# edison_mezzanine_9dof.net
KiCad netlist of a schematic drawn in EAGLE
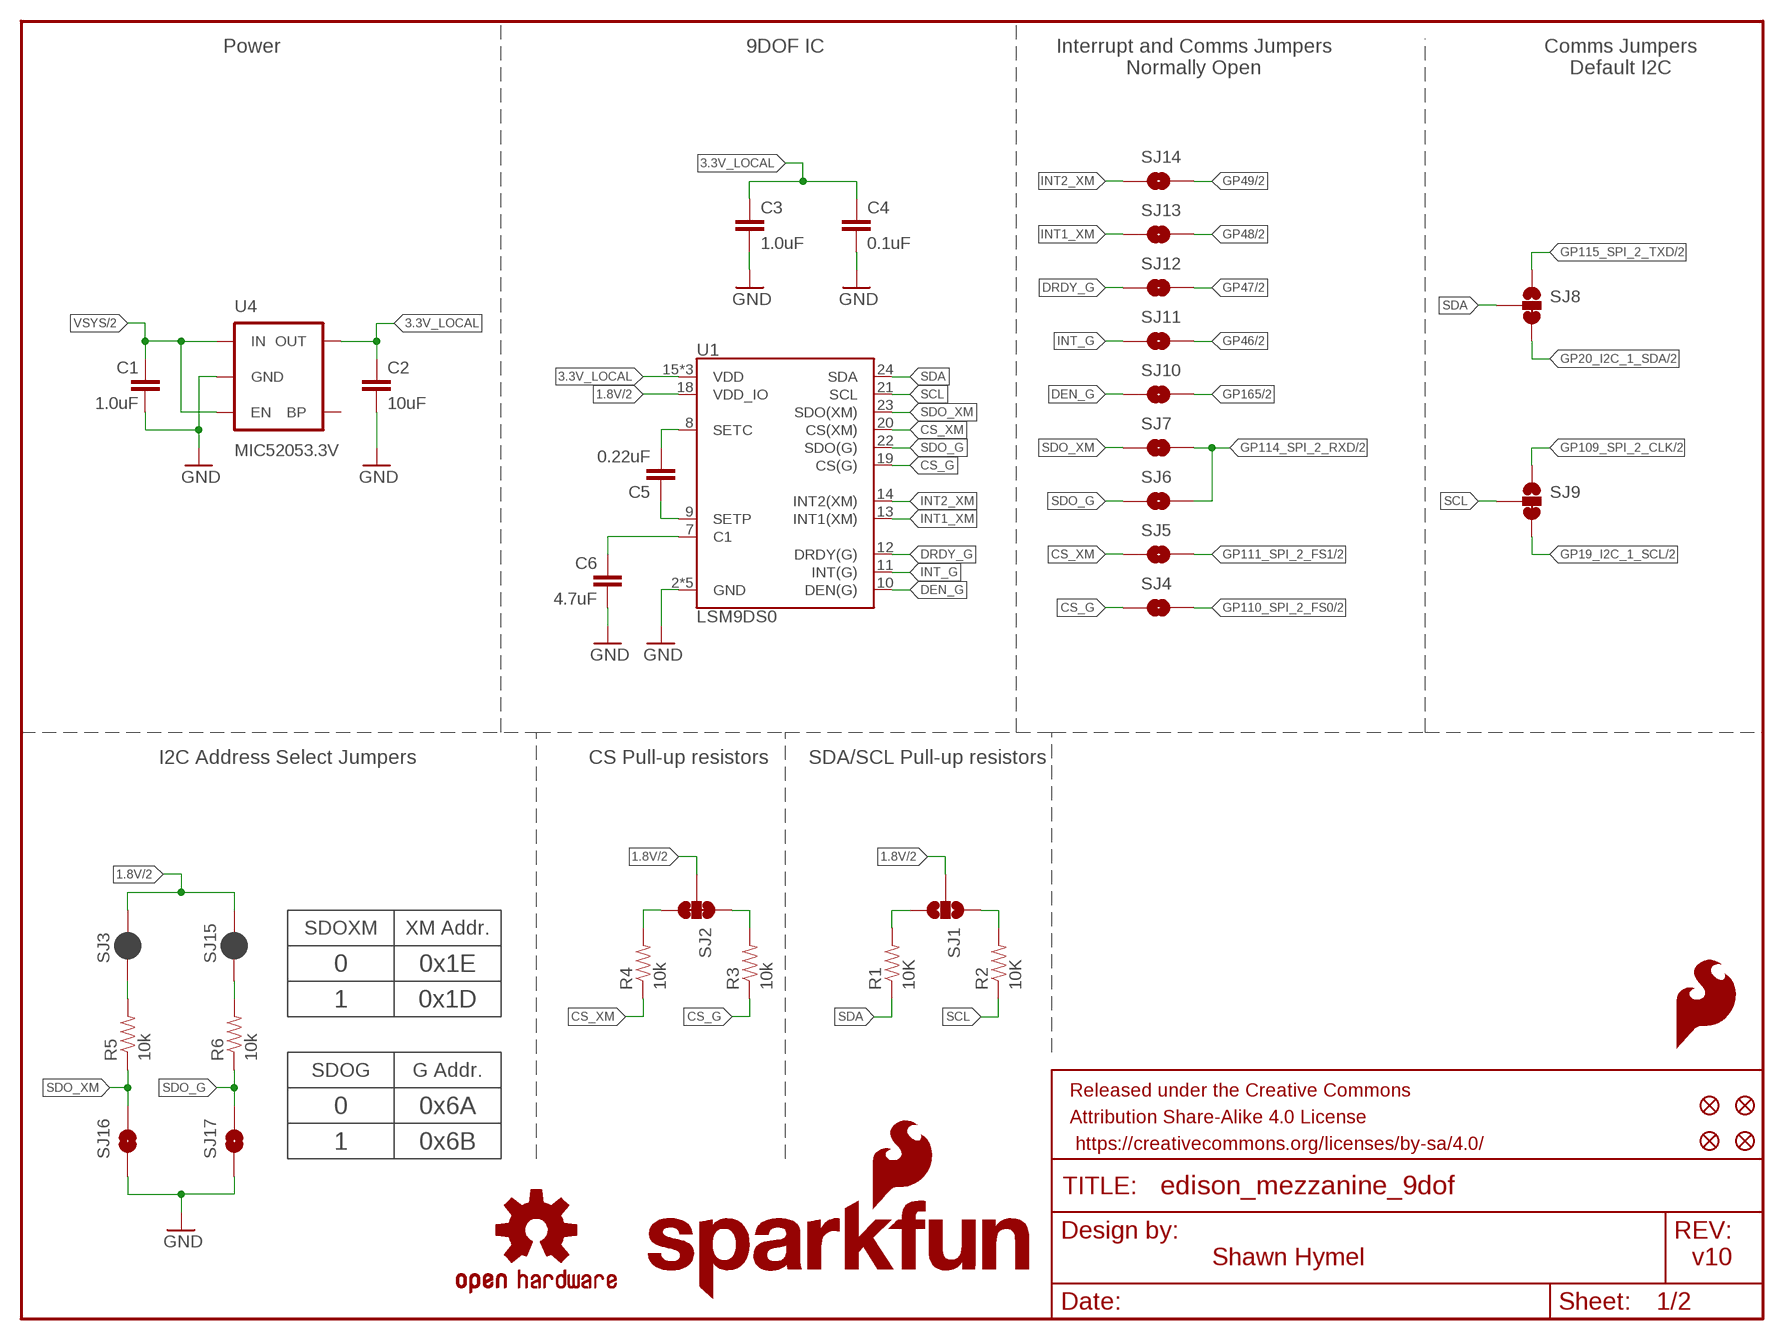
[diagram p0: schematic, sheet 1]
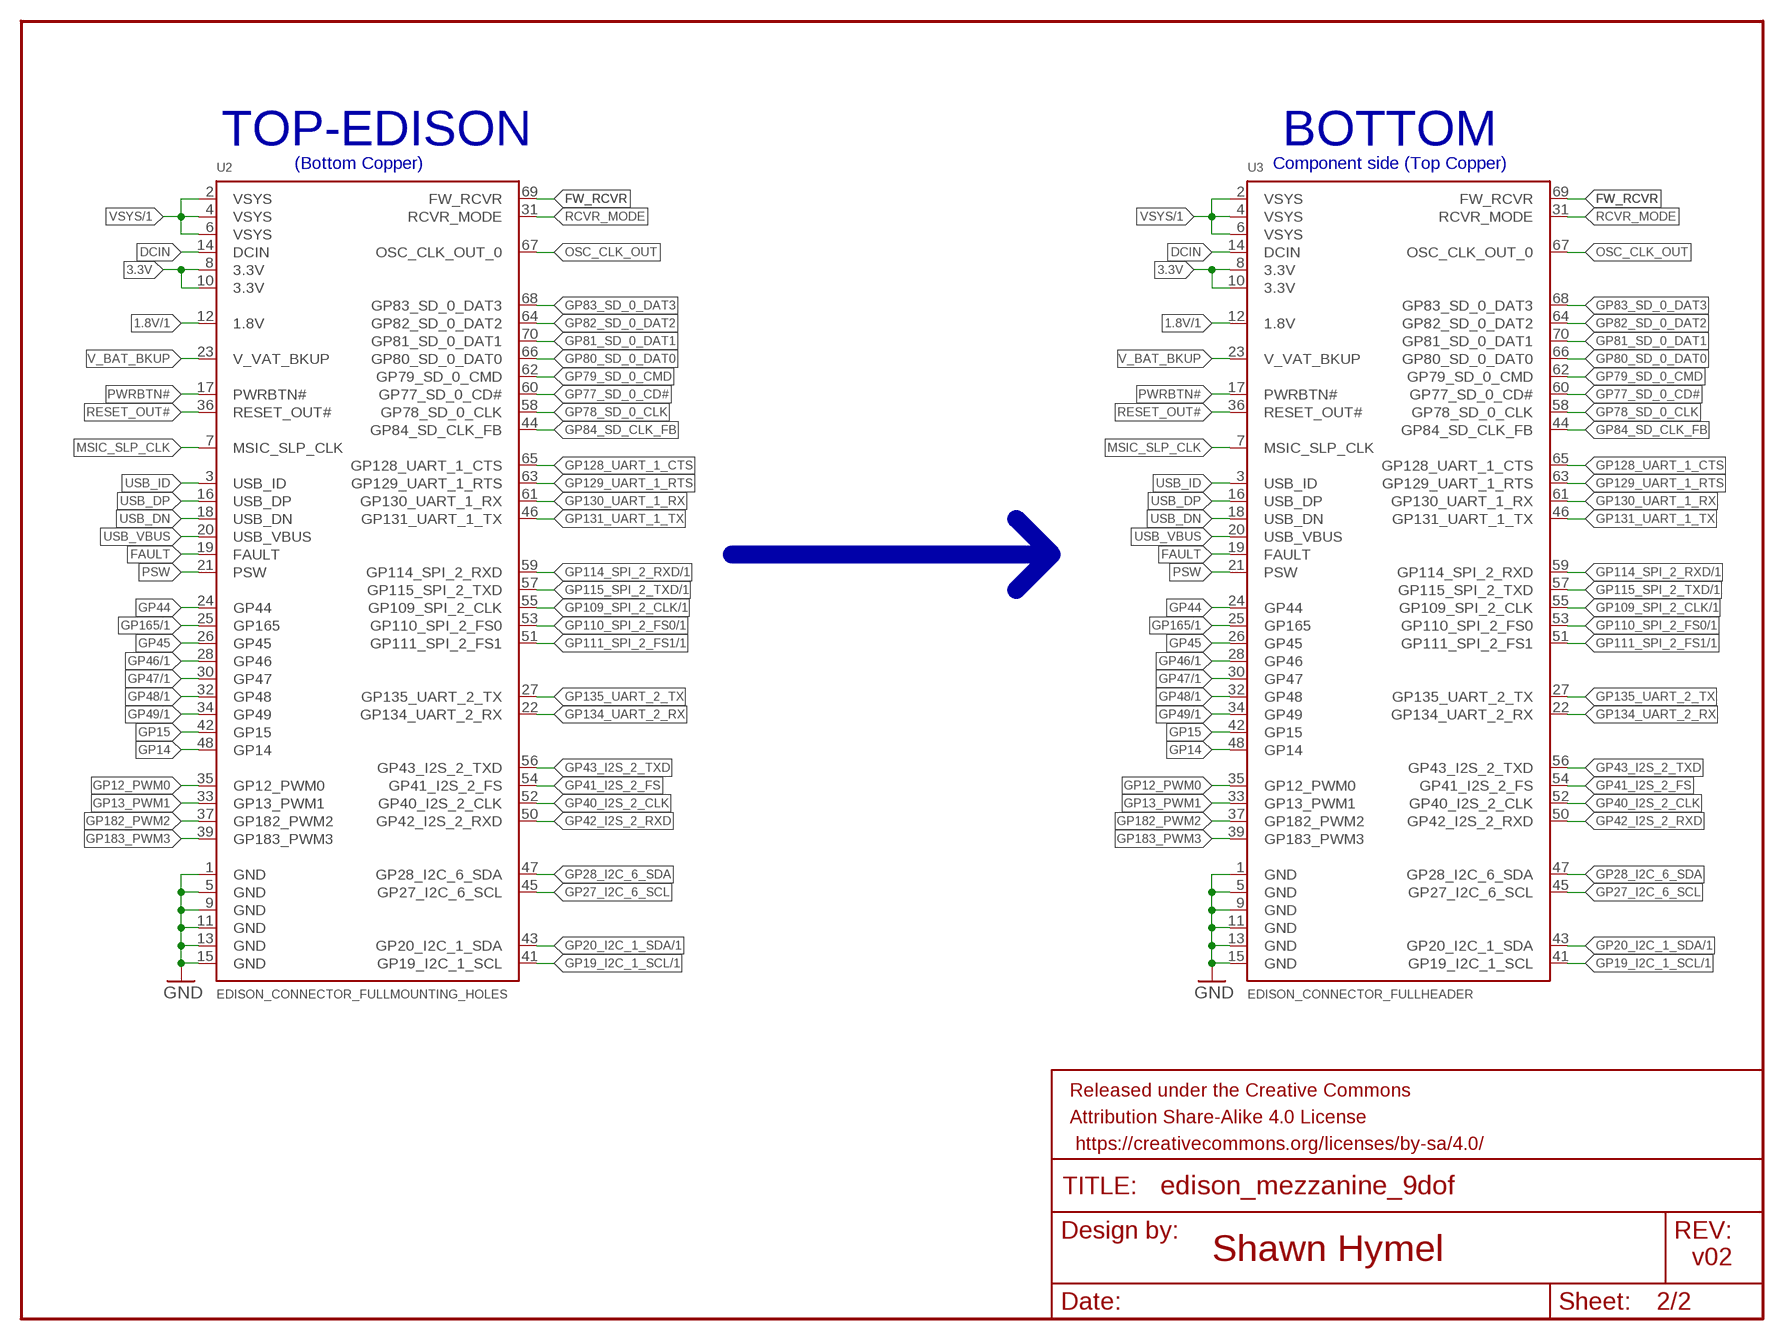
[diagram p1: schematic, sheet 2]

(export (version "E")
  (design (tool "Eeschema 10.0.6"))
  (components
    (comp (ref "C1")
      (value "1.0uF")
      (footprint "eagle-import:0603-CAP")
      (libsource (lib "eagle-import") (part "1.0UF-16V-10%(0603)"))
    )
    (comp (ref "C2")
      (value "10uF")
      (footprint "eagle-import:0805")
      (libsource (lib "eagle-import") (part "CAP0805"))
    )
    (comp (ref "C3")
      (value "1.0uF")
      (footprint "eagle-import:0603-CAP")
      (libsource (lib "eagle-import") (part "1.0UF-16V-10%(0603)"))
    )
    (comp (ref "C4")
      (value "0.1uF")
      (footprint "eagle-import:0603-CAP")
      (libsource (lib "eagle-import") (part "0.1UF-25V(+80/-20%)(0603)"))
    )
    (comp (ref "C5")
      (value "0.22uF")
      (footprint "eagle-import:0603-CAP")
      (libsource (lib "eagle-import") (part "0.22UF-25V-10%(0603)"))
    )
    (comp (ref "C6")
      (value "4.7uF")
      (footprint "eagle-import:0603-CAP")
      (libsource (lib "eagle-import") (part "4.7UF-6.3V-10%(0603)0603"))
    )
    (comp (ref "FID1")
      (value "FIDUCIAL1X2")
      (footprint "eagle-import:FIDUCIAL-1X2")
      (libsource (lib "eagle-import") (part "FIDUCIAL1X2"))
    )
    (comp (ref "FID2")
      (value "FIDUCIAL1X2")
      (footprint "eagle-import:FIDUCIAL-1X2")
      (libsource (lib "eagle-import") (part "FIDUCIAL1X2"))
    )
    (comp (ref "FID3")
      (value "FIDUCIAL1X2")
      (footprint "eagle-import:FIDUCIAL-1X2")
      (libsource (lib "eagle-import") (part "FIDUCIAL1X2"))
    )
    (comp (ref "FID4")
      (value "FIDUCIAL1X2")
      (footprint "eagle-import:FIDUCIAL-1X2")
      (libsource (lib "eagle-import") (part "FIDUCIAL1X2"))
    )
    (comp (ref "FRAME1")
      (value "FRAME-LETTER")
      (footprint "eagle-import:CREATIVE_COMMONS")
      (libsource (lib "eagle-import") (part "FRAME-LETTER"))
    )
    (comp (ref "LOGO1")
      (value "SFE_LOGO_FLAME.2_INCH")
      (footprint "eagle-import:SFE_LOGO_FLAME_.2")
      (libsource (lib "eagle-import") (part "SFE_LOGO_FLAME.2_INCH"))
    )
    (comp (ref "LOGO2")
      (value "OSHW-LOGOS")
      (footprint "eagle-import:OSHW-LOGO-S")
      (libsource (lib "eagle-import") (part "OSHW-LOGOS"))
    )
    (comp (ref "LOGO3")
      (value "SFE_LOGO_NAME_FLAME.1_INCH")
      (footprint "eagle-import:SFE_LOGO_NAME_FLAME_.1")
      (libsource (lib "eagle-import") (part "SFE_LOGO_NAME_FLAME.1_INCH"))
    )
    (comp (ref "R1")
      (value "10K")
      (footprint "eagle-import:0603-RES")
      (libsource (lib "eagle-import") (part "10KOHM1/10W1%(0603)0603"))
    )
    (comp (ref "R2")
      (value "10K")
      (footprint "eagle-import:0603-RES")
      (libsource (lib "eagle-import") (part "10KOHM1/10W1%(0603)0603"))
    )
    (comp (ref "R3")
      (value "10k")
      (footprint "eagle-import:0603-RES")
      (libsource (lib "eagle-import") (part "10K-1%RES-00824"))
    )
    (comp (ref "R4")
      (value "10k")
      (footprint "eagle-import:0603-RES")
      (libsource (lib "eagle-import") (part "10K-1%RES-00824"))
    )
    (comp (ref "R5")
      (value "10k")
      (footprint "eagle-import:0603-RES")
      (libsource (lib "eagle-import") (part "10K-1%RES-00824"))
    )
    (comp (ref "R6")
      (value "10k")
      (footprint "eagle-import:0603-RES")
      (libsource (lib "eagle-import") (part "10K-1%RES-00824"))
    )
    (comp (ref "SJ1")
      (value "JUMPER-PAD-3-NOYES_SILK")
      (footprint "eagle-import:PAD-JUMPER-3-NO_YES_SILK")
      (libsource (lib "eagle-import") (part "JUMPER-PAD-3-NOYES_SILK"))
    )
    (comp (ref "SJ2")
      (value "JUMPER-PAD-3-NC_BY_TRACE")
      (footprint "eagle-import:PAD-JUMPER-3-3OF3_NC_BY_TRACE_YES_SILK_FULL_BOX")
      (libsource (lib "eagle-import") (part "JUMPER-PAD-3-NC_BY_TRACE"))
    )
    (comp (ref "SJ3")
      (value "JUMPER-PAD-2-NC_BY_PASTE")
      (footprint "eagle-import:PAD-JUMPER-2-NC_BY_PASTE_YES_SILK")
      (libsource (lib "eagle-import") (part "JUMPER-PAD-2-NC_BY_PASTE"))
    )
    (comp (ref "SJ4")
      (value "JUMPER-PAD-2-NOYES_SILK")
      (footprint "eagle-import:PAD-JUMPER-2-NO_YES_SILK")
      (libsource (lib "eagle-import") (part "JUMPER-PAD-2-NOYES_SILK"))
    )
    (comp (ref "SJ5")
      (value "JUMPER-PAD-2-NOYES_SILK")
      (footprint "eagle-import:PAD-JUMPER-2-NO_YES_SILK")
      (libsource (lib "eagle-import") (part "JUMPER-PAD-2-NOYES_SILK"))
    )
    (comp (ref "SJ6")
      (value "JUMPER-PAD-2-NOYES_SILK")
      (footprint "eagle-import:PAD-JUMPER-2-NO_YES_SILK")
      (libsource (lib "eagle-import") (part "JUMPER-PAD-2-NOYES_SILK"))
    )
    (comp (ref "SJ7")
      (value "JUMPER-PAD-2-NOYES_SILK")
      (footprint "eagle-import:PAD-JUMPER-2-NO_YES_SILK")
      (libsource (lib "eagle-import") (part "JUMPER-PAD-2-NOYES_SILK"))
    )
    (comp (ref "SJ8")
      (value "JUMPER-PAD-3-2OF3_NC_BY_TRACE_SMALL")
      (footprint "eagle-import:PAD-JUMPER-3-2OF3_NC_BY_TRACE_YES_SILK_FULL_BOX")
      (libsource (lib "eagle-import") (part "JUMPER-PAD-3-2OF3_NC_BY_TRACE_SMALL"))
    )
    (comp (ref "SJ9")
      (value "JUMPER-PAD-3-2OF3_NC_BY_TRACE_SMALL")
      (footprint "eagle-import:PAD-JUMPER-3-2OF3_NC_BY_TRACE_YES_SILK_FULL_BOX")
      (libsource (lib "eagle-import") (part "JUMPER-PAD-3-2OF3_NC_BY_TRACE_SMALL"))
    )
    (comp (ref "SJ10")
      (value "JUMPER-PAD-2-NOYES_SILK")
      (footprint "eagle-import:PAD-JUMPER-2-NO_YES_SILK")
      (libsource (lib "eagle-import") (part "JUMPER-PAD-2-NOYES_SILK"))
    )
    (comp (ref "SJ11")
      (value "JUMPER-PAD-2-NOYES_SILK")
      (footprint "eagle-import:PAD-JUMPER-2-NO_YES_SILK")
      (libsource (lib "eagle-import") (part "JUMPER-PAD-2-NOYES_SILK"))
    )
    (comp (ref "SJ12")
      (value "JUMPER-PAD-2-NOYES_SILK")
      (footprint "eagle-import:PAD-JUMPER-2-NO_YES_SILK")
      (libsource (lib "eagle-import") (part "JUMPER-PAD-2-NOYES_SILK"))
    )
    (comp (ref "SJ13")
      (value "JUMPER-PAD-2-NOYES_SILK")
      (footprint "eagle-import:PAD-JUMPER-2-NO_YES_SILK")
      (libsource (lib "eagle-import") (part "JUMPER-PAD-2-NOYES_SILK"))
    )
    (comp (ref "SJ14")
      (value "JUMPER-PAD-2-NOYES_SILK")
      (footprint "eagle-import:PAD-JUMPER-2-NO_YES_SILK")
      (libsource (lib "eagle-import") (part "JUMPER-PAD-2-NOYES_SILK"))
    )
    (comp (ref "SJ15")
      (value "JUMPER-PAD-2-NC_BY_PASTE")
      (footprint "eagle-import:PAD-JUMPER-2-NC_BY_PASTE_YES_SILK")
      (libsource (lib "eagle-import") (part "JUMPER-PAD-2-NC_BY_PASTE"))
    )
    (comp (ref "SJ16")
      (value "JUMPER-PAD-2-NOYES_SILK")
      (footprint "eagle-import:PAD-JUMPER-2-NO_YES_SILK")
      (libsource (lib "eagle-import") (part "JUMPER-PAD-2-NOYES_SILK"))
    )
    (comp (ref "SJ17")
      (value "JUMPER-PAD-2-NOYES_SILK")
      (footprint "eagle-import:PAD-JUMPER-2-NO_YES_SILK")
      (libsource (lib "eagle-import") (part "JUMPER-PAD-2-NOYES_SILK"))
    )
    (comp (ref "U1")
      (value "LSM9DS0")
      (footprint "eagle-import:LGA-24")
      (libsource (lib "eagle-import") (part "LSM9DS0"))
    )
    (comp (ref "U4")
      (value "MIC52053.3V")
      (footprint "eagle-import:SOT23-5")
      (libsource (lib "eagle-import") (part "MIC52053.3V"))
    )
    (comp (ref "FRAME2")
      (value "FRAME-LETTER")
      (footprint "eagle-import:CREATIVE_COMMONS")
      (libsource (lib "eagle-import") (part "FRAME-LETTER"))
    )
    (comp (ref "U2")
      (value "EDISON_CONNECTOR_FULLMOUNTING_HOLES")
      (footprint "eagle-import:EDISON_DAUGHTER")
      (libsource (lib "eagle-import") (part "EDISON_CONNECTOR_FULLMOUNTING_HOLES"))
    )
    (comp (ref "U3")
      (value "EDISON_CONNECTOR_FULLHEADER")
      (footprint "eagle-import:DF40C-70DP-0.4(51)")
      (libsource (lib "eagle-import") (part "EDISON_CONNECTOR_FULLHEADER"))
    )
  )
  (nets
    (net (code "1") (name "1.8V") (class "Default")
      (node (ref "SJ1") (pin "2") (pinfunction "2_2") (pintype "passive"))
      (node (ref "SJ15") (pin "2") (pinfunction "2_2") (pintype "passive"))
      (node (ref "SJ2") (pin "2") (pinfunction "2_2") (pintype "passive"))
      (node (ref "SJ3") (pin "2") (pinfunction "2_2") (pintype "passive"))
      (node (ref "U1") (pin "18") (pinfunction "VDD_IO_18") (pintype "bidirectional"))
      (node (ref "U2") (pin "12") (pinfunction "1.8V_12") (pintype "bidirectional"))
      (node (ref "U3") (pin "12") (pinfunction "1.8V_12") (pintype "bidirectional"))
    )
    (net (code "2") (name "3.3V") (class "Default")
      (node (ref "U2") (pin "10") (pinfunction "3.3V_10") (pintype "bidirectional"))
      (node (ref "U2") (pin "8") (pinfunction "3.3V_8") (pintype "bidirectional"))
      (node (ref "U3") (pin "10") (pinfunction "3.3V_10") (pintype "bidirectional"))
      (node (ref "U3") (pin "8") (pinfunction "3.3V_8") (pintype "bidirectional"))
    )
    (net (code "3") (name "3.3V_LOCAL") (class "Default")
      (node (ref "C2") (pin "1") (pinfunction "1_1") (pintype "passive"))
      (node (ref "C3") (pin "1") (pinfunction "1_1") (pintype "passive"))
      (node (ref "C4") (pin "1") (pinfunction "1_1") (pintype "passive"))
      (node (ref "U1") (pin "15") (pinfunction "VDD_15") (pintype "bidirectional"))
      (node (ref "U1") (pin "16") (pinfunction "VDD_16") (pintype "bidirectional"))
      (node (ref "U1") (pin "17") (pinfunction "VDD_17") (pintype "bidirectional"))
      (node (ref "U4") (pin "5") (pinfunction "OUT_5") (pintype "passive"))
    )
    (net (code "4") (name "CS_G") (class "Default")
      (node (ref "R3") (pin "1") (pinfunction "1_1") (pintype "passive"))
      (node (ref "SJ4") (pin "1") (pinfunction "1_1") (pintype "passive"))
      (node (ref "U1") (pin "19") (pinfunction "CS(G)_19") (pintype "bidirectional"))
    )
    (net (code "5") (name "CS_XM") (class "Default")
      (node (ref "R4") (pin "1") (pinfunction "1_1") (pintype "passive"))
      (node (ref "SJ5") (pin "1") (pinfunction "1_1") (pintype "passive"))
      (node (ref "U1") (pin "20") (pinfunction "CS(XM)_20") (pintype "bidirectional"))
    )
    (net (code "6") (name "DCIN") (class "Default")
      (node (ref "U2") (pin "14") (pinfunction "DCIN_14") (pintype "bidirectional"))
      (node (ref "U3") (pin "14") (pinfunction "DCIN_14") (pintype "bidirectional"))
    )
    (net (code "7") (name "DEN_G") (class "Default")
      (node (ref "SJ10") (pin "1") (pinfunction "1_1") (pintype "passive"))
      (node (ref "U1") (pin "10") (pinfunction "DEN(G)_10") (pintype "bidirectional"))
    )
    (net (code "8") (name "DRDY_G") (class "Default")
      (node (ref "SJ12") (pin "1") (pinfunction "1_1") (pintype "passive"))
      (node (ref "U1") (pin "12") (pinfunction "DRDY(G)_12") (pintype "bidirectional"))
    )
    (net (code "9") (name "FAULT") (class "Default")
      (node (ref "U2") (pin "19") (pinfunction "FAULT_19") (pintype "bidirectional"))
      (node (ref "U3") (pin "19") (pinfunction "FAULT_19") (pintype "bidirectional"))
    )
    (net (code "10") (name "FW_RCVR") (class "Default")
      (node (ref "U2") (pin "69") (pinfunction "FW_RCVR_69") (pintype "bidirectional"))
      (node (ref "U3") (pin "69") (pinfunction "FW_RCVR_69") (pintype "bidirectional"))
    )
    (net (code "11") (name "GND") (class "Default")
      (node (ref "C1") (pin "2") (pinfunction "2_2") (pintype "passive"))
      (node (ref "C2") (pin "2") (pinfunction "2_2") (pintype "passive"))
      (node (ref "C3") (pin "2") (pinfunction "2_2") (pintype "passive"))
      (node (ref "C4") (pin "2") (pinfunction "2_2") (pintype "passive"))
      (node (ref "C6") (pin "2") (pinfunction "2_2") (pintype "passive"))
      (node (ref "SJ16") (pin "1") (pinfunction "1_1") (pintype "passive"))
      (node (ref "SJ17") (pin "1") (pinfunction "1_1") (pintype "passive"))
      (node (ref "U1") (pin "2") (pinfunction "GND_2") (pintype "bidirectional"))
      (node (ref "U1") (pin "3") (pinfunction "GND_3") (pintype "bidirectional"))
      (node (ref "U1") (pin "4") (pinfunction "GND_4") (pintype "bidirectional"))
      (node (ref "U1") (pin "5") (pinfunction "GND_5") (pintype "bidirectional"))
      (node (ref "U1") (pin "6") (pinfunction "GND_6") (pintype "bidirectional"))
      (node (ref "U2") (pin "1") (pinfunction "GND_1") (pintype "bidirectional"))
      (node (ref "U2") (pin "11") (pinfunction "GND_11") (pintype "bidirectional"))
      (node (ref "U2") (pin "13") (pinfunction "GND_13") (pintype "bidirectional"))
      (node (ref "U2") (pin "15") (pinfunction "GND_15") (pintype "bidirectional"))
      (node (ref "U2") (pin "5") (pinfunction "GND_5") (pintype "bidirectional"))
      (node (ref "U2") (pin "9") (pinfunction "GND_9") (pintype "bidirectional"))
      (node (ref "U3") (pin "1") (pinfunction "GND_1") (pintype "bidirectional"))
      (node (ref "U3") (pin "11") (pinfunction "GND_11") (pintype "bidirectional"))
      (node (ref "U3") (pin "13") (pinfunction "GND_13") (pintype "bidirectional"))
      (node (ref "U3") (pin "15") (pinfunction "GND_15") (pintype "bidirectional"))
      (node (ref "U3") (pin "5") (pinfunction "GND_5") (pintype "bidirectional"))
      (node (ref "U3") (pin "9") (pinfunction "GND_9") (pintype "bidirectional"))
      (node (ref "U4") (pin "2") (pinfunction "GND_2") (pintype "input"))
    )
    (net (code "12") (name "GP12_PWM0") (class "Default")
      (node (ref "U2") (pin "35") (pinfunction "GP12_PWM0_35") (pintype "bidirectional"))
      (node (ref "U3") (pin "35") (pinfunction "GP12_PWM0_35") (pintype "bidirectional"))
    )
    (net (code "13") (name "GP13_PWM1") (class "Default")
      (node (ref "U2") (pin "33") (pinfunction "GP13_PWM1_33") (pintype "bidirectional"))
      (node (ref "U3") (pin "33") (pinfunction "GP13_PWM1_33") (pintype "bidirectional"))
    )
    (net (code "14") (name "GP14") (class "Default")
      (node (ref "U2") (pin "48") (pinfunction "GP14_48") (pintype "bidirectional"))
      (node (ref "U3") (pin "48") (pinfunction "GP14_48") (pintype "bidirectional"))
    )
    (net (code "15") (name "GP15") (class "Default")
      (node (ref "U2") (pin "42") (pinfunction "GP15_42") (pintype "bidirectional"))
      (node (ref "U3") (pin "42") (pinfunction "GP15_42") (pintype "bidirectional"))
    )
    (net (code "16") (name "GP19_I2C_1_SCL") (class "Default")
      (node (ref "SJ9") (pin "3") (pinfunction "3_3") (pintype "passive"))
      (node (ref "U2") (pin "41") (pinfunction "GP19_I2C_1_SCL_41") (pintype "bidirectional"))
      (node (ref "U3") (pin "41") (pinfunction "GP19_I2C_1_SCL_41") (pintype "bidirectional"))
    )
    (net (code "17") (name "GP20_I2C_1_SDA") (class "Default")
      (node (ref "SJ8") (pin "3") (pinfunction "3_3") (pintype "passive"))
      (node (ref "U2") (pin "43") (pinfunction "GP20_I2C_1_SDA_43") (pintype "bidirectional"))
      (node (ref "U3") (pin "43") (pinfunction "GP20_I2C_1_SDA_43") (pintype "bidirectional"))
    )
    (net (code "18") (name "GP27_I2C_6_SCL") (class "Default")
      (node (ref "U2") (pin "45") (pinfunction "GP27_I2C_6_SCL_45") (pintype "bidirectional"))
      (node (ref "U3") (pin "45") (pinfunction "GP27_I2C_6_SCL_45") (pintype "bidirectional"))
    )
    (net (code "19") (name "GP28_I2C_6_SDA") (class "Default")
      (node (ref "U2") (pin "47") (pinfunction "GP28_I2C_6_SDA_47") (pintype "bidirectional"))
      (node (ref "U3") (pin "47") (pinfunction "GP28_I2C_6_SDA_47") (pintype "bidirectional"))
    )
    (net (code "20") (name "GP40_I2S_2_CLK") (class "Default")
      (node (ref "U2") (pin "52") (pinfunction "GP40_I2S_2_CLK_52") (pintype "bidirectional"))
      (node (ref "U3") (pin "52") (pinfunction "GP40_I2S_2_CLK_52") (pintype "bidirectional"))
    )
    (net (code "21") (name "GP41_I2S_2_FS") (class "Default")
      (node (ref "U2") (pin "54") (pinfunction "GP41_I2S_2_FS_54") (pintype "bidirectional"))
      (node (ref "U3") (pin "54") (pinfunction "GP41_I2S_2_FS_54") (pintype "bidirectional"))
    )
    (net (code "22") (name "GP42_I2S_2_RXD") (class "Default")
      (node (ref "U2") (pin "50") (pinfunction "GP42_I2S_2_RXD_50") (pintype "bidirectional"))
      (node (ref "U3") (pin "50") (pinfunction "GP42_I2S_2_RXD_50") (pintype "bidirectional"))
    )
    (net (code "23") (name "GP43_I2S_2_TXD") (class "Default")
      (node (ref "U2") (pin "56") (pinfunction "GP43_I2S_2_TXD_56") (pintype "bidirectional"))
      (node (ref "U3") (pin "56") (pinfunction "GP43_I2S_2_TXD_56") (pintype "bidirectional"))
    )
    (net (code "24") (name "GP44") (class "Default")
      (node (ref "U2") (pin "24") (pinfunction "GP44_24") (pintype "bidirectional"))
      (node (ref "U3") (pin "24") (pinfunction "GP44_24") (pintype "bidirectional"))
    )
    (net (code "25") (name "GP45") (class "Default")
      (node (ref "U2") (pin "26") (pinfunction "GP45_26") (pintype "bidirectional"))
      (node (ref "U3") (pin "26") (pinfunction "GP45_26") (pintype "bidirectional"))
    )
    (net (code "26") (name "GP46") (class "Default")
      (node (ref "SJ11") (pin "2") (pinfunction "2_2") (pintype "passive"))
      (node (ref "U2") (pin "28") (pinfunction "GP46_28") (pintype "bidirectional"))
      (node (ref "U3") (pin "28") (pinfunction "GP46_28") (pintype "bidirectional"))
    )
    (net (code "27") (name "GP47") (class "Default")
      (node (ref "SJ12") (pin "2") (pinfunction "2_2") (pintype "passive"))
      (node (ref "U2") (pin "30") (pinfunction "GP47_30") (pintype "bidirectional"))
      (node (ref "U3") (pin "30") (pinfunction "GP47_30") (pintype "bidirectional"))
    )
    (net (code "28") (name "GP48") (class "Default")
      (node (ref "SJ13") (pin "2") (pinfunction "2_2") (pintype "passive"))
      (node (ref "U2") (pin "32") (pinfunction "GP48_32") (pintype "bidirectional"))
      (node (ref "U3") (pin "32") (pinfunction "GP48_32") (pintype "bidirectional"))
    )
    (net (code "29") (name "GP49") (class "Default")
      (node (ref "SJ14") (pin "2") (pinfunction "2_2") (pintype "passive"))
      (node (ref "U2") (pin "34") (pinfunction "GP49_34") (pintype "bidirectional"))
      (node (ref "U3") (pin "34") (pinfunction "GP49_34") (pintype "bidirectional"))
    )
    (net (code "30") (name "GP77_SD_0_CD#") (class "Default")
      (node (ref "U2") (pin "60") (pinfunction "GP77_SD_0_CD#_60") (pintype "bidirectional"))
      (node (ref "U3") (pin "60") (pinfunction "GP77_SD_0_CD#_60") (pintype "bidirectional"))
    )
    (net (code "31") (name "GP78_SD_0_CLK") (class "Default")
      (node (ref "U2") (pin "58") (pinfunction "GP78_SD_0_CLK_58") (pintype "bidirectional"))
      (node (ref "U3") (pin "58") (pinfunction "GP78_SD_0_CLK_58") (pintype "bidirectional"))
    )
    (net (code "32") (name "GP79_SD_0_CMD") (class "Default")
      (node (ref "U2") (pin "62") (pinfunction "GP79_SD_0_CMD_62") (pintype "bidirectional"))
      (node (ref "U3") (pin "62") (pinfunction "GP79_SD_0_CMD_62") (pintype "bidirectional"))
    )
    (net (code "33") (name "GP80_SD_0_DAT0") (class "Default")
      (node (ref "U2") (pin "66") (pinfunction "GP80_SD_0_DAT0_66") (pintype "bidirectional"))
      (node (ref "U3") (pin "66") (pinfunction "GP80_SD_0_DAT0_66") (pintype "bidirectional"))
    )
    (net (code "34") (name "GP81_SD_0_DAT1") (class "Default")
      (node (ref "U2") (pin "70") (pinfunction "GP81_SD_0_DAT1_70") (pintype "bidirectional"))
      (node (ref "U3") (pin "70") (pinfunction "GP81_SD_0_DAT1_70") (pintype "bidirectional"))
    )
    (net (code "35") (name "GP82_SD_0_DAT2") (class "Default")
      (node (ref "U2") (pin "64") (pinfunction "GP82_SD_0_DAT2_64") (pintype "bidirectional"))
      (node (ref "U3") (pin "64") (pinfunction "GP82_SD_0_DAT2_64") (pintype "bidirectional"))
    )
    (net (code "36") (name "GP83_SD_0_DAT3") (class "Default")
      (node (ref "U2") (pin "68") (pinfunction "GP83_SD_0_DAT3_68") (pintype "bidirectional"))
      (node (ref "U3") (pin "68") (pinfunction "GP83_SD_0_DAT3_68") (pintype "bidirectional"))
    )
    (net (code "37") (name "GP84_SD_CLK_FB") (class "Default")
      (node (ref "U2") (pin "44") (pinfunction "GP84_SD_CLK_FB_44") (pintype "bidirectional"))
      (node (ref "U3") (pin "44") (pinfunction "GP84_SD_CLK_FB_44") (pintype "bidirectional"))
    )
    (net (code "38") (name "GP109_SPI_2_CLK") (class "Default")
      (node (ref "SJ9") (pin "1") (pinfunction "1_1") (pintype "passive"))
      (node (ref "U2") (pin "55") (pinfunction "GP109_SPI_2_CLK_55") (pintype "bidirectional"))
      (node (ref "U3") (pin "55") (pinfunction "GP109_SPI_2_CLK_55") (pintype "bidirectional"))
    )
    (net (code "39") (name "GP110_SPI_2_FS0") (class "Default")
      (node (ref "SJ4") (pin "2") (pinfunction "2_2") (pintype "passive"))
      (node (ref "U2") (pin "53") (pinfunction "GP110_SPI_2_FS0_53") (pintype "bidirectional"))
      (node (ref "U3") (pin "53") (pinfunction "GP110_SPI_2_FS0_53") (pintype "bidirectional"))
    )
    (net (code "40") (name "GP111_SPI_2_FS1") (class "Default")
      (node (ref "SJ5") (pin "2") (pinfunction "2_2") (pintype "passive"))
      (node (ref "U2") (pin "51") (pinfunction "GP111_SPI_2_FS1_51") (pintype "bidirectional"))
      (node (ref "U3") (pin "51") (pinfunction "GP111_SPI_2_FS1_51") (pintype "bidirectional"))
    )
    (net (code "41") (name "GP114_SPI_2_RXD") (class "Default")
      (node (ref "SJ6") (pin "2") (pinfunction "2_2") (pintype "passive"))
      (node (ref "SJ7") (pin "2") (pinfunction "2_2") (pintype "passive"))
      (node (ref "U2") (pin "59") (pinfunction "GP114_SPI_2_RXD_59") (pintype "bidirectional"))
      (node (ref "U3") (pin "59") (pinfunction "GP114_SPI_2_RXD_59") (pintype "bidirectional"))
    )
    (net (code "42") (name "GP115_SPI_2_TXD") (class "Default")
      (node (ref "SJ8") (pin "1") (pinfunction "1_1") (pintype "passive"))
      (node (ref "U2") (pin "57") (pinfunction "GP115_SPI_2_TXD_57") (pintype "bidirectional"))
      (node (ref "U3") (pin "57") (pinfunction "GP115_SPI_2_TXD_57") (pintype "bidirectional"))
    )
    (net (code "43") (name "GP128_UART_1_CTS") (class "Default")
      (node (ref "U2") (pin "65") (pinfunction "GP128_UART_1_CTS_65") (pintype "bidirectional"))
      (node (ref "U3") (pin "65") (pinfunction "GP128_UART_1_CTS_65") (pintype "bidirectional"))
    )
    (net (code "44") (name "GP129_UART_1_RTS") (class "Default")
      (node (ref "U2") (pin "63") (pinfunction "GP129_UART_1_RTS_63") (pintype "bidirectional"))
      (node (ref "U3") (pin "63") (pinfunction "GP129_UART_1_RTS_63") (pintype "bidirectional"))
    )
    (net (code "45") (name "GP130_UART_1_RX") (class "Default")
      (node (ref "U2") (pin "61") (pinfunction "GP130_UART_1_RX_61") (pintype "bidirectional"))
      (node (ref "U3") (pin "61") (pinfunction "GP130_UART_1_RX_61") (pintype "bidirectional"))
    )
    (net (code "46") (name "GP131_UART_1_TX") (class "Default")
      (node (ref "U2") (pin "46") (pinfunction "GP131_UART_1_TX_46") (pintype "bidirectional"))
      (node (ref "U3") (pin "46") (pinfunction "GP131_UART_1_TX_46") (pintype "bidirectional"))
    )
    (net (code "47") (name "GP134_UART_2_RX") (class "Default")
      (node (ref "U2") (pin "22") (pinfunction "GP134_UART_2_RX_22") (pintype "bidirectional"))
      (node (ref "U3") (pin "22") (pinfunction "GP134_UART_2_RX_22") (pintype "bidirectional"))
    )
    (net (code "48") (name "GP135_UART_2_TX") (class "Default")
      (node (ref "U2") (pin "27") (pinfunction "GP135_UART_2_TX_27") (pintype "bidirectional"))
      (node (ref "U3") (pin "27") (pinfunction "GP135_UART_2_TX_27") (pintype "bidirectional"))
    )
    (net (code "49") (name "GP165") (class "Default")
      (node (ref "SJ10") (pin "2") (pinfunction "2_2") (pintype "passive"))
      (node (ref "U2") (pin "25") (pinfunction "GP165_25") (pintype "bidirectional"))
      (node (ref "U3") (pin "25") (pinfunction "GP165_25") (pintype "bidirectional"))
    )
    (net (code "50") (name "GP182_PWM2") (class "Default")
      (node (ref "U2") (pin "37") (pinfunction "GP182_PWM2_37") (pintype "bidirectional"))
      (node (ref "U3") (pin "37") (pinfunction "GP182_PWM2_37") (pintype "bidirectional"))
    )
    (net (code "51") (name "GP183_PWM3") (class "Default")
      (node (ref "U2") (pin "39") (pinfunction "GP183_PWM3_39") (pintype "bidirectional"))
      (node (ref "U3") (pin "39") (pinfunction "GP183_PWM3_39") (pintype "bidirectional"))
    )
    (net (code "52") (name "INT1_XM") (class "Default")
      (node (ref "SJ13") (pin "1") (pinfunction "1_1") (pintype "passive"))
      (node (ref "U1") (pin "13") (pinfunction "INT1(XM)_13") (pintype "bidirectional"))
    )
    (net (code "53") (name "INT2_XM") (class "Default")
      (node (ref "SJ14") (pin "1") (pinfunction "1_1") (pintype "passive"))
      (node (ref "U1") (pin "14") (pinfunction "INT2(XM)_14") (pintype "bidirectional"))
    )
    (net (code "54") (name "INT_G") (class "Default")
      (node (ref "SJ11") (pin "1") (pinfunction "1_1") (pintype "passive"))
      (node (ref "U1") (pin "11") (pinfunction "INT(G)_11") (pintype "bidirectional"))
    )
    (net (code "55") (name "MSIC_SLP_CLK") (class "Default")
      (node (ref "U2") (pin "7") (pinfunction "MSIC_SLP_CLK_7") (pintype "bidirectional"))
      (node (ref "U3") (pin "7") (pinfunction "MSIC_SLP_CLK_7") (pintype "bidirectional"))
    )
    (net (code "56") (name "Net-(R1-Pad2)") (class "Default")
      (node (ref "R1") (pin "2") (pinfunction "2_2") (pintype "passive"))
      (node (ref "SJ1") (pin "3") (pinfunction "3_3") (pintype "passive"))
    )
    (net (code "57") (name "Net-(R2-Pad2)") (class "Default")
      (node (ref "R2") (pin "2") (pinfunction "2_2") (pintype "passive"))
      (node (ref "SJ1") (pin "1") (pinfunction "1_1") (pintype "passive"))
    )
    (net (code "58") (name "Net-(R3-Pad2)") (class "Default")
      (node (ref "R3") (pin "2") (pinfunction "2_2") (pintype "passive"))
      (node (ref "SJ2") (pin "1") (pinfunction "1_1") (pintype "passive"))
    )
    (net (code "59") (name "Net-(R4-Pad2)") (class "Default")
      (node (ref "R4") (pin "2") (pinfunction "2_2") (pintype "passive"))
      (node (ref "SJ2") (pin "3") (pinfunction "3_3") (pintype "passive"))
    )
    (net (code "60") (name "Net-(R5-Pad2)") (class "Default")
      (node (ref "R5") (pin "2") (pinfunction "2_2") (pintype "passive"))
      (node (ref "SJ3") (pin "1") (pinfunction "1_1") (pintype "passive"))
    )
    (net (code "61") (name "Net-(R6-Pad2)") (class "Default")
      (node (ref "R6") (pin "2") (pinfunction "2_2") (pintype "passive"))
      (node (ref "SJ15") (pin "1") (pinfunction "1_1") (pintype "passive"))
    )
    (net (code "62") (name "Net-(U1-C1)") (class "Default")
      (node (ref "C6") (pin "1") (pinfunction "1_1") (pintype "passive"))
      (node (ref "U1") (pin "7") (pinfunction "C1_7") (pintype "bidirectional"))
    )
    (net (code "63") (name "Net-(U1-SETC)") (class "Default")
      (node (ref "C5") (pin "2") (pinfunction "2_2") (pintype "passive"))
      (node (ref "U1") (pin "8") (pinfunction "SETC_8") (pintype "bidirectional"))
    )
    (net (code "64") (name "Net-(U1-SETP)") (class "Default")
      (node (ref "C5") (pin "1") (pinfunction "1_1") (pintype "passive"))
      (node (ref "U1") (pin "9") (pinfunction "SETP_9") (pintype "bidirectional"))
    )
    (net (code "65") (name "OSC_CLK_OUT") (class "Default")
      (node (ref "U2") (pin "67") (pinfunction "OSC_CLK_OUT_0_67") (pintype "bidirectional"))
      (node (ref "U3") (pin "67") (pinfunction "OSC_CLK_OUT_0_67") (pintype "bidirectional"))
    )
    (net (code "66") (name "PSW") (class "Default")
      (node (ref "U2") (pin "21") (pinfunction "PSW_21") (pintype "bidirectional"))
      (node (ref "U3") (pin "21") (pinfunction "PSW_21") (pintype "bidirectional"))
    )
    (net (code "67") (name "PWRBTN#") (class "Default")
      (node (ref "U2") (pin "17") (pinfunction "PWRBTN#_17") (pintype "bidirectional"))
      (node (ref "U3") (pin "17") (pinfunction "PWRBTN#_17") (pintype "bidirectional"))
    )
    (net (code "68") (name "RCVR_MODE") (class "Default")
      (node (ref "U2") (pin "31") (pinfunction "RCVR_MODE_31") (pintype "bidirectional"))
      (node (ref "U3") (pin "31") (pinfunction "RCVR_MODE_31") (pintype "bidirectional"))
    )
    (net (code "69") (name "RESET_OUT#") (class "Default")
      (node (ref "U2") (pin "36") (pinfunction "RESET_OUT#_36") (pintype "bidirectional"))
      (node (ref "U3") (pin "36") (pinfunction "RESET_OUT#_36") (pintype "bidirectional"))
    )
    (net (code "70") (name "SCL") (class "Default")
      (node (ref "R2") (pin "1") (pinfunction "1_1") (pintype "passive"))
      (node (ref "SJ9") (pin "2") (pinfunction "2_2") (pintype "passive"))
      (node (ref "U1") (pin "21") (pinfunction "SCL_21") (pintype "bidirectional"))
    )
    (net (code "71") (name "SDA") (class "Default")
      (node (ref "R1") (pin "1") (pinfunction "1_1") (pintype "passive"))
      (node (ref "SJ8") (pin "2") (pinfunction "2_2") (pintype "passive"))
      (node (ref "U1") (pin "24") (pinfunction "SDA_24") (pintype "bidirectional"))
    )
    (net (code "72") (name "SDO_G") (class "Default")
      (node (ref "R6") (pin "1") (pinfunction "1_1") (pintype "passive"))
      (node (ref "SJ17") (pin "2") (pinfunction "2_2") (pintype "passive"))
      (node (ref "SJ6") (pin "1") (pinfunction "1_1") (pintype "passive"))
      (node (ref "U1") (pin "22") (pinfunction "SDO(G)_22") (pintype "bidirectional"))
    )
    (net (code "73") (name "SDO_XM") (class "Default")
      (node (ref "R5") (pin "1") (pinfunction "1_1") (pintype "passive"))
      (node (ref "SJ16") (pin "2") (pinfunction "2_2") (pintype "passive"))
      (node (ref "SJ7") (pin "1") (pinfunction "1_1") (pintype "passive"))
      (node (ref "U1") (pin "23") (pinfunction "SDO(XM)_23") (pintype "bidirectional"))
    )
    (net (code "74") (name "USB_DN") (class "Default")
      (node (ref "U2") (pin "18") (pinfunction "USB_DN_18") (pintype "bidirectional"))
      (node (ref "U3") (pin "18") (pinfunction "USB_DN_18") (pintype "bidirectional"))
    )
    (net (code "75") (name "USB_DP") (class "Default")
      (node (ref "U2") (pin "16") (pinfunction "USB_DP_16") (pintype "bidirectional"))
      (node (ref "U3") (pin "16") (pinfunction "USB_DP_16") (pintype "bidirectional"))
    )
    (net (code "76") (name "USB_ID") (class "Default")
      (node (ref "U2") (pin "3") (pinfunction "USB_ID_3") (pintype "bidirectional"))
      (node (ref "U3") (pin "3") (pinfunction "USB_ID_3") (pintype "bidirectional"))
    )
    (net (code "77") (name "USB_VBUS") (class "Default")
      (node (ref "U2") (pin "20") (pinfunction "USB_VBUS_20") (pintype "bidirectional"))
      (node (ref "U3") (pin "20") (pinfunction "USB_VBUS_20") (pintype "bidirectional"))
    )
    (net (code "78") (name "VSYS") (class "Default")
      (node (ref "C1") (pin "1") (pinfunction "1_1") (pintype "passive"))
      (node (ref "U2") (pin "2") (pinfunction "VSYS_2") (pintype "bidirectional"))
      (node (ref "U2") (pin "4") (pinfunction "VSYS_4") (pintype "bidirectional"))
      (node (ref "U2") (pin "6") (pinfunction "VSYS_6") (pintype "bidirectional"))
      (node (ref "U3") (pin "2") (pinfunction "VSYS_2") (pintype "bidirectional"))
      (node (ref "U3") (pin "4") (pinfunction "VSYS_4") (pintype "bidirectional"))
      (node (ref "U3") (pin "6") (pinfunction "VSYS_6") (pintype "bidirectional"))
      (node (ref "U4") (pin "1") (pinfunction "IN_1") (pintype "input"))
      (node (ref "U4") (pin "3") (pinfunction "EN_3") (pintype "input"))
    )
    (net (code "79") (name "V_BAT_BKUP") (class "Default")
      (node (ref "U2") (pin "23") (pinfunction "V_VAT_BKUP_23") (pintype "bidirectional"))
      (node (ref "U3") (pin "23") (pinfunction "V_VAT_BKUP_23") (pintype "bidirectional"))
    )
    (net (code "80") (name "unconnected-(U4-BP-Pad4)") (class "Default")
      (node (ref "U4") (pin "4") (pinfunction "BP_4") (pintype "input"))
    )
  )
)
